# Serial_Comms.net
KiCad netlist of a schematic drawn in Altium Designer
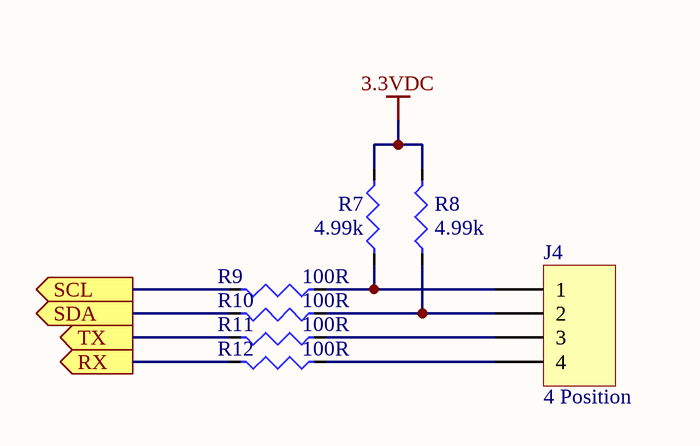
[diagram p0: Serial Comms.SchDoc]

(export (version "E")
  (design (tool "Eeschema 10.0.6"))
  (components
    (comp (ref "J4")
      (value "MTA 100 - 4 Position")
      (footprint "4POS TBLOCK_REV2")
      (description "Header, 4-Pin")
      (fields (field (name "QUICKVALUE") "4 Position"))
      (libsource (lib "EDC Standard Library") (part "Header 4"))
    )
    (comp (ref "R7")
      (value "Resistor")
      (footprint "RESISTOR THT 3W 0.05HOLE 900MIL")
      (fields (field (name "TOLERANCE") "1%") (field (name "QUICKVALUE") "4.99k"))
      (libsource (lib "EDC Standard Library") (part "Resistor"))
    )
    (comp (ref "R8")
      (value "Resistor")
      (footprint "RESISTOR THT 3W 0.05HOLE 900MIL")
      (fields (field (name "TOLERANCE") "1%") (field (name "QUICKVALUE") "4.99k"))
      (libsource (lib "EDC Standard Library") (part "Resistor"))
    )
    (comp (ref "R9")
      (value "Resistor")
      (footprint "Resistor - 0603")
      (fields (field (name "TOLERANCE") "1%") (field (name "QUICKVALUE") "100R"))
      (libsource (lib "EDC Standard Library") (part "Resistor"))
    )
    (comp (ref "R10")
      (value "Resistor")
      (footprint "Resistor - 0603")
      (fields (field (name "TOLERANCE") "1%") (field (name "QUICKVALUE") "100R"))
      (libsource (lib "EDC Standard Library") (part "Resistor"))
    )
    (comp (ref "R11")
      (value "Resistor")
      (footprint "Resistor - 0603")
      (fields (field (name "TOLERANCE") "1%") (field (name "QUICKVALUE") "100R"))
      (libsource (lib "EDC Standard Library") (part "Resistor"))
    )
    (comp (ref "R12")
      (value "Resistor")
      (footprint "Resistor - 0603")
      (fields (field (name "TOLERANCE") "1%") (field (name "QUICKVALUE") "100R"))
      (libsource (lib "EDC Standard Library") (part "Resistor"))
    )
  )
  (nets
    (net (code "1") (name "/RX") (class "Default")
      (node (ref "R12") (pin "2") (pinfunction "2_2") (pintype "passive"))
    )
    (net (code "2") (name "/SCL") (class "Default")
      (node (ref "R9") (pin "2") (pinfunction "2_2") (pintype "passive"))
    )
    (net (code "3") (name "/SDA") (class "Default")
      (node (ref "R10") (pin "2") (pinfunction "2_2") (pintype "passive"))
    )
    (net (code "4") (name "/TX") (class "Default")
      (node (ref "R11") (pin "2") (pinfunction "2_2") (pintype "passive"))
    )
    (net (code "5") (name "3.3VDC") (class "Default")
      (node (ref "R7") (pin "2") (pinfunction "2_2") (pintype "passive"))
      (node (ref "R8") (pin "2") (pinfunction "2_2") (pintype "passive"))
    )
    (net (code "6") (name "Net-(J4-Pad1)") (class "Default")
      (node (ref "J4") (pin "1") (pinfunction "1_1") (pintype "passive"))
      (node (ref "R7") (pin "1") (pinfunction "1_1") (pintype "passive"))
      (node (ref "R9") (pin "1") (pinfunction "1_1") (pintype "passive"))
    )
    (net (code "7") (name "Net-(J4-Pad2)") (class "Default")
      (node (ref "J4") (pin "2") (pinfunction "2_2") (pintype "passive"))
      (node (ref "R10") (pin "1") (pinfunction "1_1") (pintype "passive"))
      (node (ref "R8") (pin "1") (pinfunction "1_1") (pintype "passive"))
    )
    (net (code "8") (name "Net-(J4-Pad3)") (class "Default")
      (node (ref "J4") (pin "3") (pinfunction "3_3") (pintype "passive"))
      (node (ref "R11") (pin "1") (pinfunction "1_1") (pintype "passive"))
    )
    (net (code "9") (name "Net-(J4-Pad4)") (class "Default")
      (node (ref "J4") (pin "4") (pinfunction "4_4") (pintype "passive"))
      (node (ref "R12") (pin "1") (pinfunction "1_1") (pintype "passive"))
    )
  )
)
